# H-bridgeSG3525.net
KiCad netlist of a schematic drawn in EAGLE
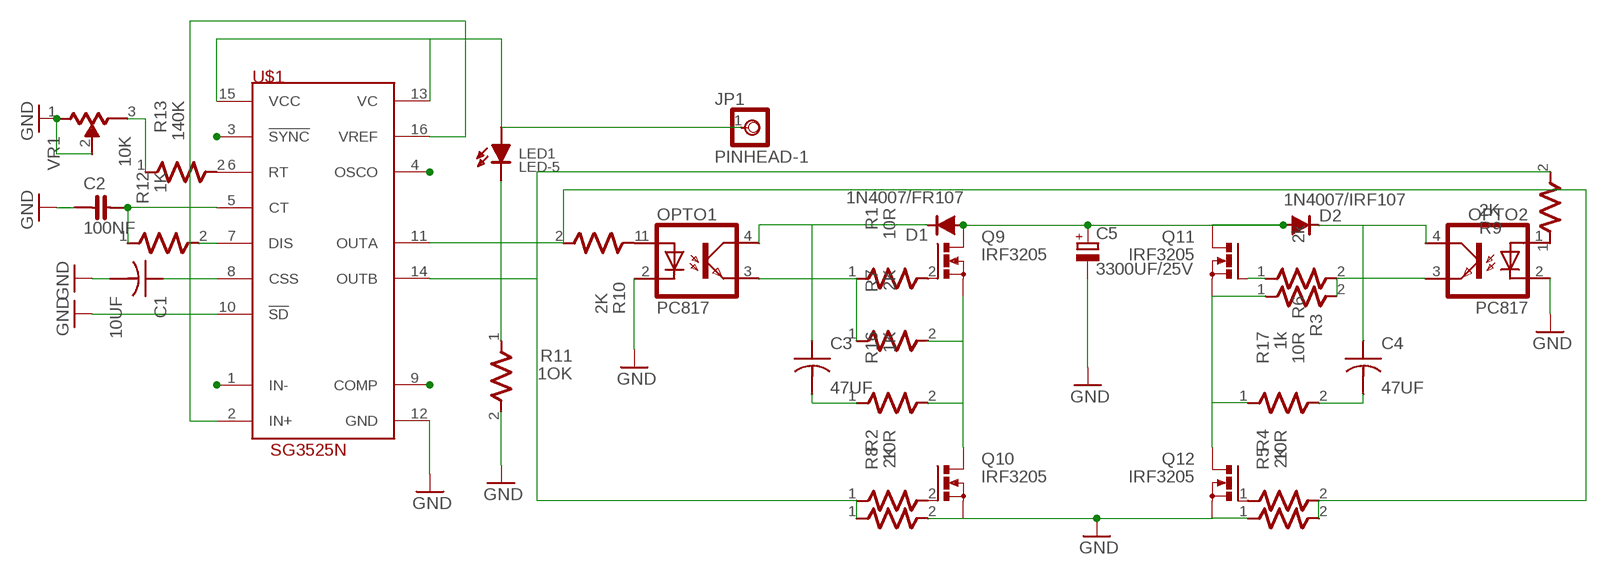
[diagram p0: schematic, sheet 1]

(export (version "E")
  (design (tool "Eeschema 10.0.6"))
  (components
    (comp (ref "C1")
      (value "10UF")
      (footprint "eagle-import:CAP-2,5")
      (libsource (lib "eagle-import") (part "CAP-2,5"))
    )
    (comp (ref "C2")
      (value "100NF")
      (footprint "eagle-import:CAP-NP5")
      (libsource (lib "eagle-import") (part "CAP-NP5"))
    )
    (comp (ref "C3")
      (value "47UF")
      (footprint "eagle-import:CAP-2,5")
      (libsource (lib "eagle-import") (part "CAP-2,5"))
    )
    (comp (ref "C4")
      (value "47UF")
      (footprint "eagle-import:CAP-2,5")
      (libsource (lib "eagle-import") (part "CAP-2,5"))
    )
    (comp (ref "C5")
      (value "3300UF/25V")
      (footprint "eagle-import:E7,5-18")
      (libsource (lib "eagle-import") (part "CPOL-EUE7.5-18"))
    )
    (comp (ref "D1")
      (value "1N4007/FR107")
      (footprint "eagle-import:1N4007")
      (libsource (lib "eagle-import") (part "1N4007"))
    )
    (comp (ref "D2")
      (value "1N4007/IRF107")
      (footprint "eagle-import:1N4007")
      (libsource (lib "eagle-import") (part "1N4007"))
    )
    (comp (ref "JP1")
      (value "PINHEAD-1")
      (footprint "eagle-import:PINHEAD-1")
      (libsource (lib "eagle-import") (part "PINHEAD-1"))
    )
    (comp (ref "LED1")
      (value "LED-5")
      (footprint "eagle-import:LED5")
      (libsource (lib "eagle-import") (part "LED-5"))
    )
    (comp (ref "OPTO1")
      (value "PC817")
      (footprint "eagle-import:DIL-04")
      (libsource (lib "eagle-import") (part "PC817"))
    )
    (comp (ref "OPTO2")
      (value "PC817")
      (footprint "eagle-import:DIL-04")
      (libsource (lib "eagle-import") (part "PC817"))
    )
    (comp (ref "Q9")
      (value "IRF3205")
      (footprint "eagle-import:TO220BV")
      (libsource (lib "eagle-import") (part "IRF512"))
    )
    (comp (ref "Q10")
      (value "IRF3205")
      (footprint "eagle-import:TO220BV")
      (libsource (lib "eagle-import") (part "IRF512"))
    )
    (comp (ref "Q11")
      (value "IRF3205")
      (footprint "eagle-import:TO220BV")
      (libsource (lib "eagle-import") (part "IRF512"))
    )
    (comp (ref "Q12")
      (value "IRF3205")
      (footprint "eagle-import:TO220BV")
      (libsource (lib "eagle-import") (part "IRF512"))
    )
    (comp (ref "R1")
      (value "10R")
      (footprint "eagle-import:R-7,5")
      (libsource (lib "eagle-import") (part "lbr_R-7,5"))
    )
    (comp (ref "R2")
      (value "10R")
      (footprint "eagle-import:R-7,5")
      (libsource (lib "eagle-import") (part "lbr_R-7,5"))
    )
    (comp (ref "R3")
      (value "10R")
      (footprint "eagle-import:R-7,5")
      (libsource (lib "eagle-import") (part "lbr_R-7,5"))
    )
    (comp (ref "R4")
      (value "10R")
      (footprint "eagle-import:R-7,5")
      (libsource (lib "eagle-import") (part "lbr_R-7,5"))
    )
    (comp (ref "R5")
      (value "2K")
      (footprint "eagle-import:R-7,5")
      (libsource (lib "eagle-import") (part "lbr_R-7,5"))
    )
    (comp (ref "R6")
      (value "2k")
      (footprint "eagle-import:R-7,5")
      (libsource (lib "eagle-import") (part "lbr_R-7,5"))
    )
    (comp (ref "R7")
      (value "2K")
      (footprint "eagle-import:R-7,5")
      (libsource (lib "eagle-import") (part "lbr_R-7,5"))
    )
    (comp (ref "R8")
      (value "2K")
      (footprint "eagle-import:R-7,5")
      (libsource (lib "eagle-import") (part "lbr_R-7,5"))
    )
    (comp (ref "R9")
      (value "2K")
      (footprint "eagle-import:R-7,5")
      (libsource (lib "eagle-import") (part "R-7,5"))
    )
    (comp (ref "R10")
      (value "2K")
      (footprint "eagle-import:R-7,5")
      (libsource (lib "eagle-import") (part "R-7,5"))
    )
    (comp (ref "R11")
      (value "1OK")
      (footprint "eagle-import:R-7,5")
      (libsource (lib "eagle-import") (part "R-7,5"))
    )
    (comp (ref "R12")
      (value "1K")
      (footprint "eagle-import:R-7,5")
      (libsource (lib "eagle-import") (part "R-7,5"))
    )
    (comp (ref "R13")
      (value "140K")
      (footprint "eagle-import:R-7,5")
      (libsource (lib "eagle-import") (part "R-7,5"))
    )
    (comp (ref "R16")
      (value "1K")
      (footprint "eagle-import:R-7,5")
      (libsource (lib "eagle-import") (part "lbr_R-7,5"))
    )
    (comp (ref "R17")
      (value "1k")
      (footprint "eagle-import:R-7,5")
      (libsource (lib "eagle-import") (part "lbr_R-7,5"))
    )
    (comp (ref "U$1")
      (value "SG3525N")
      (footprint "eagle-import:DIL16")
      (libsource (lib "eagle-import") (part "SG3525N"))
    )
    (comp (ref "VR1")
      (value "10K")
      (footprint "eagle-import:VR-5")
      (libsource (lib "eagle-import") (part "VR-5"))
    )
  )
  (nets
    (net (code "1") (name "/COMP") (class "Default")
      (node (ref "U$1") (pin "9") (pinfunction "COMP_9") (pintype "power_in"))
    )
    (net (code "2") (name "/IN-") (class "Default")
      (node (ref "U$1") (pin "1") (pinfunction "IN-_1") (pintype "power_in"))
    )
    (net (code "3") (name "GND") (class "Default")
      (node (ref "C1") (pin "-") (pinfunction "2_-") (pintype "passive"))
      (node (ref "C2") (pin "1") (pinfunction "1_1") (pintype "passive"))
      (node (ref "C5") (pin "-") (pinfunction "-_-") (pintype "passive"))
      (node (ref "OPTO1") (pin "2") (pinfunction "C_2") (pintype "passive"))
      (node (ref "OPTO2") (pin "2") (pinfunction "C_2") (pintype "passive"))
      (node (ref "Q10") (pin "S") (pinfunction "S_S") (pintype "passive"))
      (node (ref "Q12") (pin "S") (pinfunction "S_S") (pintype "passive"))
      (node (ref "R11") (pin "2") (pinfunction "2_2") (pintype "passive"))
      (node (ref "R5") (pin "1") (pinfunction "1_1") (pintype "passive"))
      (node (ref "R8") (pin "2") (pinfunction "2_2") (pintype "passive"))
      (node (ref "U$1") (pin "10") (pinfunction "~{SD}_10") (pintype "input"))
      (node (ref "U$1") (pin "12") (pinfunction "GND_12") (pintype "power_in"))
      (node (ref "VR1") (pin "1") (pinfunction "1_1") (pintype "passive"))
      (node (ref "VR1") (pin "2") (pinfunction "2_2") (pintype "passive"))
    )
    (net (code "4") (name "Net-(C1-1)") (class "Default")
      (node (ref "C1") (pin "+") (pinfunction "1_+") (pintype "passive"))
      (node (ref "U$1") (pin "8") (pinfunction "CSS_8") (pintype "power_in"))
    )
    (net (code "5") (name "Net-(C3-1)") (class "Default")
      (node (ref "C3") (pin "+") (pinfunction "1_+") (pintype "passive"))
      (node (ref "D1") (pin "K") (pinfunction "K_K") (pintype "passive"))
      (node (ref "OPTO1") (pin "4") (pinfunction "COL_4") (pintype "passive"))
    )
    (net (code "6") (name "Net-(C3-2)") (class "Default")
      (node (ref "C3") (pin "-") (pinfunction "2_-") (pintype "passive"))
      (node (ref "R16") (pin "1") (pinfunction "1_1") (pintype "passive"))
    )
    (net (code "7") (name "Net-(C4-1)") (class "Default")
      (node (ref "C4") (pin "+") (pinfunction "1_+") (pintype "passive"))
      (node (ref "D2") (pin "K") (pinfunction "K_K") (pintype "passive"))
      (node (ref "OPTO2") (pin "4") (pinfunction "COL_4") (pintype "passive"))
    )
    (net (code "8") (name "Net-(C4-2)") (class "Default")
      (node (ref "C4") (pin "-") (pinfunction "2_-") (pintype "passive"))
      (node (ref "R17") (pin "2") (pinfunction "2_2") (pintype "passive"))
    )
    (net (code "9") (name "Net-(C5-Pad+)") (class "Default")
      (node (ref "C5") (pin "+") (pinfunction "+_+") (pintype "passive"))
      (node (ref "D1") (pin "A") (pinfunction "A_A") (pintype "passive"))
      (node (ref "D2") (pin "A") (pinfunction "A_A") (pintype "passive"))
      (node (ref "Q11") (pin "D") (pinfunction "D_D") (pintype "passive"))
      (node (ref "Q9") (pin "D") (pinfunction "D_D") (pintype "passive"))
    )
    (net (code "10") (name "Net-(LED1-PadK)") (class "Default")
      (node (ref "LED1") (pin "K") (pinfunction "K_K") (pintype "passive"))
      (node (ref "R11") (pin "1") (pinfunction "1_1") (pintype "passive"))
    )
    (net (code "11") (name "Net-(OPTO1-A)") (class "Default")
      (node (ref "OPTO1") (pin "1") (pinfunction "A_1") (pintype "passive"))
      (node (ref "R10") (pin "1") (pinfunction "1_1") (pintype "passive"))
    )
    (net (code "12") (name "Net-(OPTO1-EMI)") (class "Default")
      (node (ref "OPTO1") (pin "3") (pinfunction "EMI_3") (pintype "passive"))
      (node (ref "R1") (pin "1") (pinfunction "1_1") (pintype "passive"))
      (node (ref "R7") (pin "1") (pinfunction "1_1") (pintype "passive"))
    )
    (net (code "13") (name "Net-(OPTO2-A)") (class "Default")
      (node (ref "OPTO2") (pin "1") (pinfunction "A_1") (pintype "passive"))
      (node (ref "R9") (pin "1") (pinfunction "1_1") (pintype "passive"))
    )
    (net (code "14") (name "Net-(OPTO2-EMI)") (class "Default")
      (node (ref "OPTO2") (pin "3") (pinfunction "EMI_3") (pintype "passive"))
      (node (ref "R3") (pin "2") (pinfunction "2_2") (pintype "passive"))
      (node (ref "R6") (pin "2") (pinfunction "2_2") (pintype "passive"))
    )
    (net (code "15") (name "Net-(Q9-PadG)") (class "Default")
      (node (ref "Q9") (pin "G") (pinfunction "G_G") (pintype "passive"))
      (node (ref "R1") (pin "2") (pinfunction "2_2") (pintype "passive"))
    )
    (net (code "16") (name "Net-(Q10-PadD)") (class "Default")
      (node (ref "Q10") (pin "D") (pinfunction "D_D") (pintype "passive"))
      (node (ref "Q9") (pin "S") (pinfunction "S_S") (pintype "passive"))
      (node (ref "R16") (pin "2") (pinfunction "2_2") (pintype "passive"))
      (node (ref "R7") (pin "2") (pinfunction "2_2") (pintype "passive"))
    )
    (net (code "17") (name "Net-(Q10-PadG)") (class "Default")
      (node (ref "Q10") (pin "G") (pinfunction "G_G") (pintype "passive"))
      (node (ref "R2") (pin "2") (pinfunction "2_2") (pintype "passive"))
    )
    (net (code "18") (name "Net-(Q11-PadG)") (class "Default")
      (node (ref "Q11") (pin "G") (pinfunction "G_G") (pintype "passive"))
      (node (ref "R3") (pin "1") (pinfunction "1_1") (pintype "passive"))
    )
    (net (code "19") (name "Net-(Q11-PadS)") (class "Default")
      (node (ref "Q11") (pin "S") (pinfunction "S_S") (pintype "passive"))
      (node (ref "Q12") (pin "D") (pinfunction "D_D") (pintype "passive"))
      (node (ref "R17") (pin "1") (pinfunction "1_1") (pintype "passive"))
      (node (ref "R6") (pin "1") (pinfunction "1_1") (pintype "passive"))
    )
    (net (code "20") (name "Net-(Q12-PadG)") (class "Default")
      (node (ref "Q12") (pin "G") (pinfunction "G_G") (pintype "passive"))
      (node (ref "R4") (pin "1") (pinfunction "1_1") (pintype "passive"))
    )
    (net (code "21") (name "Net-(R13-Pad1)") (class "Default")
      (node (ref "R13") (pin "1") (pinfunction "1_1") (pintype "passive"))
      (node (ref "VR1") (pin "3") (pinfunction "3_3") (pintype "passive"))
    )
    (net (code "22") (name "Net-(U$1-CT)") (class "Default")
      (node (ref "C2") (pin "2") (pinfunction "2_2") (pintype "passive"))
      (node (ref "R12") (pin "1") (pinfunction "1_1") (pintype "passive"))
      (node (ref "U$1") (pin "5") (pinfunction "CT_5") (pintype "input"))
    )
    (net (code "23") (name "Net-(U$1-DIS)") (class "Default")
      (node (ref "R12") (pin "2") (pinfunction "2_2") (pintype "passive"))
      (node (ref "U$1") (pin "7") (pinfunction "DIS_7") (pintype "output"))
    )
    (net (code "24") (name "Net-(U$1-IN+)") (class "Default")
      (node (ref "U$1") (pin "16") (pinfunction "VREF_16") (pintype "power_in"))
      (node (ref "U$1") (pin "2") (pinfunction "IN+_2") (pintype "output"))
    )
    (net (code "25") (name "Net-(U$1-OUTA)") (class "Default")
      (node (ref "R10") (pin "2") (pinfunction "2_2") (pintype "passive"))
      (node (ref "R4") (pin "2") (pinfunction "2_2") (pintype "passive"))
      (node (ref "R5") (pin "2") (pinfunction "2_2") (pintype "passive"))
      (node (ref "U$1") (pin "11") (pinfunction "OUTA_11") (pintype "power_in"))
    )
    (net (code "26") (name "Net-(U$1-OUTB)") (class "Default")
      (node (ref "R2") (pin "1") (pinfunction "1_1") (pintype "passive"))
      (node (ref "R8") (pin "1") (pinfunction "1_1") (pintype "passive"))
      (node (ref "R9") (pin "2") (pinfunction "2_2") (pintype "passive"))
      (node (ref "U$1") (pin "14") (pinfunction "OUTB_14") (pintype "power_in"))
    )
    (net (code "27") (name "Net-(U$1-RT)") (class "Default")
      (node (ref "R13") (pin "2") (pinfunction "2_2") (pintype "passive"))
      (node (ref "U$1") (pin "6") (pinfunction "RT_6") (pintype "output"))
    )
    (net (code "28") (name "Net-(U$1-VC)") (class "Default")
      (node (ref "JP1") (pin "1") (pinfunction "1_1") (pintype "passive"))
      (node (ref "LED1") (pin "A") (pinfunction "A_A") (pintype "passive"))
      (node (ref "U$1") (pin "13") (pinfunction "VC_13") (pintype "power_in"))
      (node (ref "U$1") (pin "15") (pinfunction "VCC_15") (pintype "power_in"))
    )
    (net (code "29") (name "unconnected-(U$1-OSCO-Pad4)") (class "Default")
      (node (ref "U$1") (pin "4") (pinfunction "OSCO_4") (pintype "output"))
    )
    (net (code "30") (name "unconnected-(U$1-~{SYNC}-Pad3)") (class "Default")
      (node (ref "U$1") (pin "3") (pinfunction "~{SYNC}_3") (pintype "output"))
    )
  )
)
